# PowerLatch.net
KiCad netlist of a schematic drawn in Altium Designer
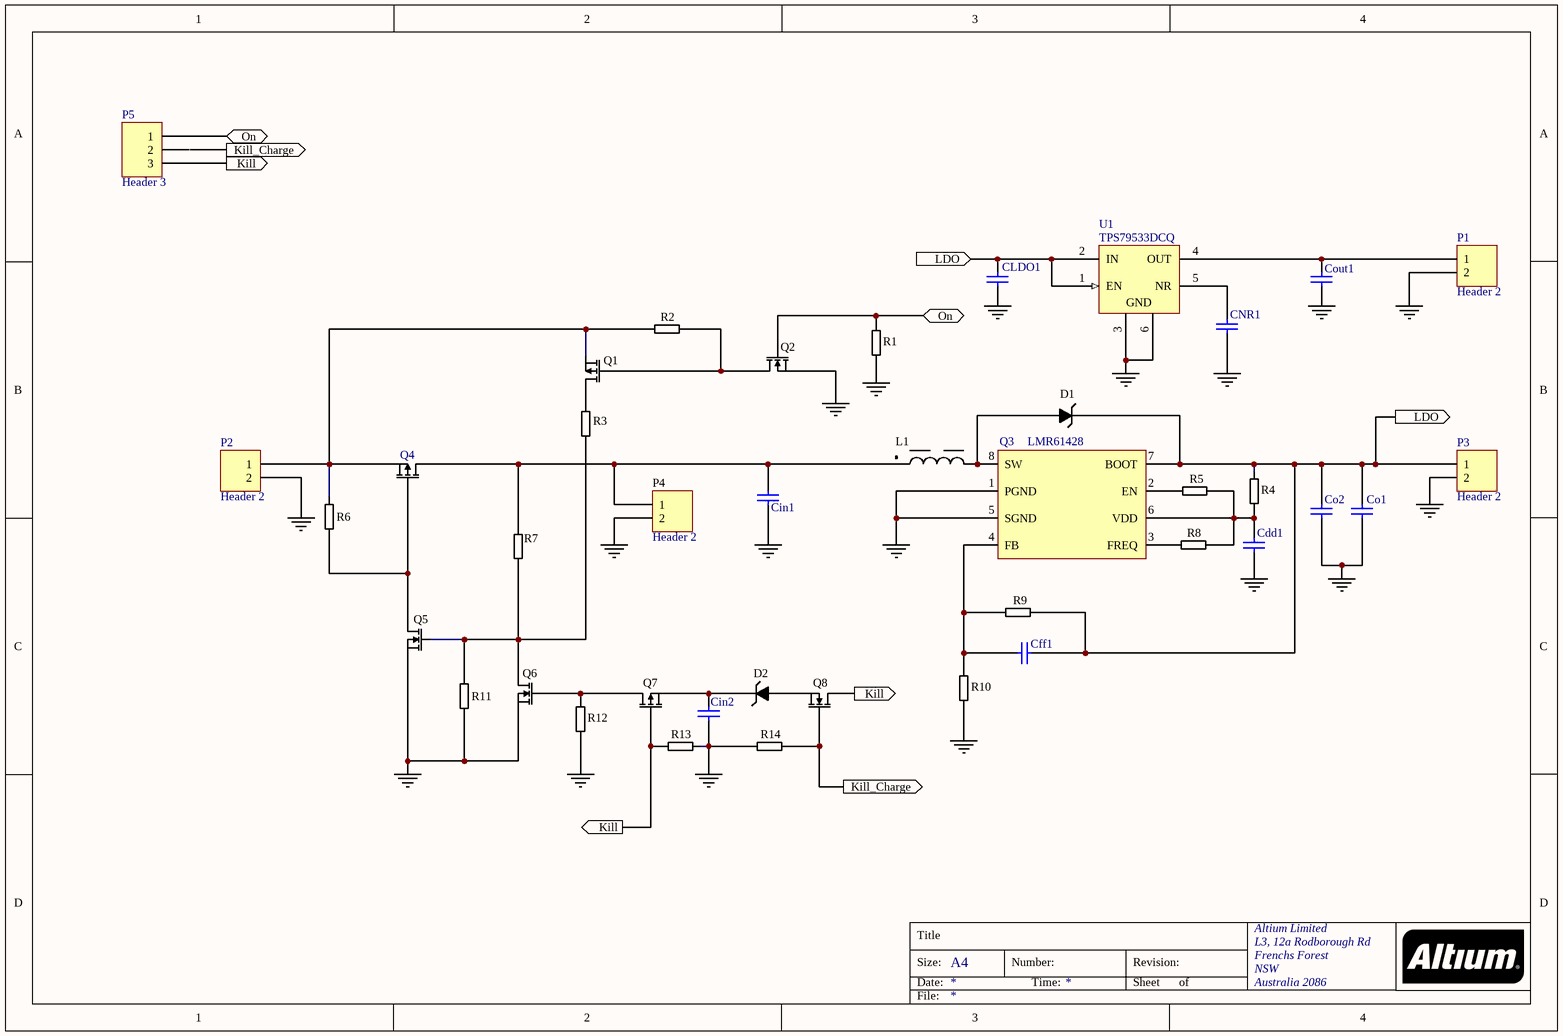
[diagram p0: PowerLatch.SchDoc]

(export (version "E")
  (design (tool "Eeschema 10.0.6"))
  (components
    (comp (ref "Cdd1")
      (value "Cap")
      (footprint "RESC1608X06N")
      (description "Capacitor")
      (fields (field (name "PUBLISHER") "Altium Limited"))
      (libsource (lib "Miscellaneous Devices") (part "Cap"))
    )
    (comp (ref "Cff1")
      (value "Cap")
      (footprint "RESC1608X06N")
      (description "Capacitor")
      (fields (field (name "PUBLISHER") "Altium Limited"))
      (libsource (lib "Miscellaneous Devices") (part "Cap"))
    )
    (comp (ref "Cin1")
      (value "Cap")
      (footprint "CAPMP7343X31N")
      (description "Capacitor")
      (fields (field (name "PUBLISHER") "Altium Limited"))
      (libsource (lib "Miscellaneous Devices") (part "Cap"))
    )
    (comp (ref "Cin2")
      (value "Cap")
      (footprint "CAPMP7343X31N")
      (description "Capacitor")
      (fields (field (name "PUBLISHER") "Altium Limited"))
      (libsource (lib "Miscellaneous Devices") (part "Cap"))
    )
    (comp (ref "CLDO1")
      (value "Cap")
      (footprint "RESC1608X06N")
      (description "Capacitor")
      (fields (field (name "PUBLISHER") "Altium Limited"))
      (libsource (lib "Miscellaneous Devices") (part "Cap"))
    )
    (comp (ref "CNR1")
      (value "Cap")
      (footprint "RESC1608X06N")
      (description "Capacitor")
      (fields (field (name "PUBLISHER") "Altium Limited"))
      (libsource (lib "Miscellaneous Devices") (part "Cap"))
    )
    (comp (ref "Co1")
      (value "Cap")
      (footprint "CAPC0805")
      (description "Capacitor")
      (fields (field (name "PUBLISHER") "Altium Limited"))
      (libsource (lib "Miscellaneous Devices") (part "Cap"))
    )
    (comp (ref "Co2")
      (value "Cap")
      (footprint "CAP2812")
      (description "Capacitor")
      (fields (field (name "PUBLISHER") "Altium Limited"))
      (libsource (lib "Miscellaneous Devices") (part "Cap"))
    )
    (comp (ref "Cout1")
      (value "Cap")
      (footprint "RESC1608X06N")
      (description "Capacitor")
      (fields (field (name "PUBLISHER") "Altium Limited"))
      (libsource (lib "Miscellaneous Devices") (part "Cap"))
    )
    (comp (ref "D1")
      (value "Schottky")
      (footprint "DIOM4326X23N")
      (libsource (lib "Schlib1") (part "Schottky"))
    )
    (comp (ref "D2")
      (value "Schottky")
      (footprint "DIOM4326X23N")
      (libsource (lib "Schlib1") (part "Schottky"))
    )
    (comp (ref "L1")
      (value "Inductor")
      (footprint "INDP100100X51N")
      (libsource (lib "Schlib1") (part "Inductor"))
    )
    (comp (ref "P1")
      (value "Header 2")
      (footprint "PCBComponent_1")
      (description "Header, 2-Pin")
      (fields (field (name "PUBLISHER") "Altium Limited"))
      (libsource (lib "") (part "Header 2_1"))
    )
    (comp (ref "P2")
      (value "Header 2")
      (footprint "PCBComponent_1")
      (description "Header, 2-Pin")
      (fields (field (name "PUBLISHER") "Altium Limited"))
      (libsource (lib "Miscellaneous Connectors") (part "Header 2"))
    )
    (comp (ref "P3")
      (value "Header 2")
      (footprint "PCBComponent_1")
      (description "Header, 2-Pin")
      (fields (field (name "PUBLISHER") "Altium Limited"))
      (libsource (lib "") (part "Header 2_1"))
    )
    (comp (ref "P4")
      (value "Header 2")
      (footprint "PCBComponent_1")
      (description "Header, 2-Pin")
      (fields (field (name "PUBLISHER") "Altium Limited"))
      (libsource (lib "") (part "Header 2_1"))
    )
    (comp (ref "P5")
      (value "Header 3")
      (footprint "HDR1X3")
      (description "Header, 3-Pin")
      (fields (field (name "PUBLISHER") "Altium Limited"))
      (libsource (lib "Miscellaneous Connectors") (part "Header 3"))
    )
    (comp (ref "Q1")
      (value "MOSFET P-Channel")
      (footprint "SOT95P245X110-3N")
      (libsource (lib "Schlib1") (part "MOSFET P-Channel"))
    )
    (comp (ref "Q2")
      (value "MOSFET N-Channel")
      (footprint "SOT95P245X110-3N")
      (libsource (lib "Schlib1") (part "MOSFET N-Channel"))
    )
    (comp (ref "Q3")
      (value "LMR61428")
      (footprint "TSOP65P490X110-8N")
      (description "Step-Up Voltage Regulator")
      (libsource (lib "Schlib1") (part "LMR61428"))
    )
    (comp (ref "Q4")
      (value "MOSFET P-Channel")
      (footprint "SOT95P245X110-3N")
      (libsource (lib "Schlib1") (part "MOSFET P-Channel"))
    )
    (comp (ref "Q5")
      (value "MOSFET N-Channel")
      (footprint "SOT95P245X110-3N")
      (libsource (lib "Schlib1") (part "MOSFET N-Channel"))
    )
    (comp (ref "Q6")
      (value "MOSFET N-Channel")
      (footprint "SOT95P245X110-3N")
      (libsource (lib "Schlib1") (part "MOSFET N-Channel"))
    )
    (comp (ref "Q7")
      (value "MOSFET P-Channel")
      (footprint "SOT95P245X110-3N")
      (libsource (lib "Schlib1") (part "MOSFET P-Channel"))
    )
    (comp (ref "Q8")
      (value "MOSFET N-Channel")
      (footprint "SOT95P245X110-3N")
      (libsource (lib "Schlib1") (part "MOSFET N-Channel"))
    )
    (comp (ref "R1") (value "Res?") (libsource (lib "Schlib1") (part "Res?")))
    (comp (ref "R2") (value "Res?") (libsource (lib "Schlib1") (part "Res?")))
    (comp (ref "R3") (value "Res?") (libsource (lib "Schlib1") (part "Res?")))
    (comp (ref "R4") (value "Res?") (libsource (lib "Schlib1") (part "Res?")))
    (comp (ref "R5") (value "Res?") (libsource (lib "Schlib1") (part "Res?")))
    (comp (ref "R6") (value "Res?") (libsource (lib "Schlib1") (part "Res?")))
    (comp (ref "R7") (value "Res?") (libsource (lib "Schlib1") (part "Res?")))
    (comp (ref "R8") (value "Res?") (libsource (lib "Schlib1") (part "Res?")))
    (comp (ref "R9") (value "Res?") (libsource (lib "Schlib1") (part "Res?")))
    (comp (ref "R10") (value "Res?") (libsource (lib "Schlib1") (part "Res?")))
    (comp (ref "R11") (value "Res?") (libsource (lib "Schlib1") (part "Res?")))
    (comp (ref "R12") (value "Res?") (libsource (lib "Schlib1") (part "Res?")))
    (comp (ref "R13") (value "Res?") (libsource (lib "Schlib1") (part "Res?")))
    (comp (ref "R14") (value "Res?") (libsource (lib "Schlib1") (part "Res?")))
    (comp (ref "U1")
      (value "TPS79533DCQ")
      (footprint "DCQ0006A_L")
      (fields (field (name "MANUFACTURER") "Texas Instruments"))
      (libsource (lib "Altium Content Vault") (part "TI-TPS7XXXXXXXX"))
    )
  )
  (nets
    (net (code "1") (name "/Kill") (class "Default")
      (node (ref "P5") (pin "3") (pinfunction "3_3") (pintype "passive"))
      (node (ref "Q7") (pin "1") (pinfunction "G_1") (pintype "passive"))
      (node (ref "Q8") (pin "3") (pinfunction "D_3") (pintype "passive"))
      (node (ref "R13") (pin "2") (pinfunction "2_2") (pintype "passive"))
    )
    (net (code "2") (name "/Kill_Charge") (class "Default")
      (node (ref "Q8") (pin "1") (pinfunction "G_1") (pintype "passive"))
      (node (ref "R14") (pin "1") (pinfunction "1_1") (pintype "passive"))
    )
    (net (code "3") (name "/LDO") (class "Default")
      (node (ref "CLDO1") (pin "2") (pinfunction "2_2") (pintype "passive"))
      (node (ref "Cff1") (pin "1") (pinfunction "1_1") (pintype "passive"))
      (node (ref "Co1") (pin "2") (pinfunction "2_2") (pintype "passive"))
      (node (ref "Co2") (pin "1") (pinfunction "1_1") (pintype "passive"))
      (node (ref "D1") (pin "2") (pinfunction "K_2") (pintype "passive"))
      (node (ref "P3") (pin "1") (pinfunction "1_1") (pintype "passive"))
      (node (ref "Q3") (pin "7") (pinfunction "BOOT_7") (pintype "passive"))
      (node (ref "R4") (pin "2") (pinfunction "2_2") (pintype "passive"))
      (node (ref "R9") (pin "1") (pinfunction "1_1") (pintype "passive"))
      (node (ref "U1") (pin "1") (pinfunction "EN_1") (pintype "input"))
      (node (ref "U1") (pin "2") (pinfunction "IN_2") (pintype "power_in"))
    )
    (net (code "4") (name "/On") (class "Default")
      (node (ref "P5") (pin "1") (pinfunction "1_1") (pintype "passive"))
      (node (ref "Q2") (pin "1") (pinfunction "G_1") (pintype "passive"))
      (node (ref "R1") (pin "2") (pinfunction "2_2") (pintype "passive"))
    )
    (net (code "5") (name "GND") (class "Default")
      (node (ref "CLDO1") (pin "1") (pinfunction "1_1") (pintype "passive"))
      (node (ref "CNR1") (pin "1") (pinfunction "1_1") (pintype "passive"))
      (node (ref "Cdd1") (pin "1") (pinfunction "1_1") (pintype "passive"))
      (node (ref "Cin1") (pin "2") (pinfunction "2_2") (pintype "passive"))
      (node (ref "Cin2") (pin "2") (pinfunction "2_2") (pintype "passive"))
      (node (ref "Co1") (pin "1") (pinfunction "1_1") (pintype "passive"))
      (node (ref "Co2") (pin "2") (pinfunction "2_2") (pintype "passive"))
      (node (ref "Cout1") (pin "1") (pinfunction "1_1") (pintype "passive"))
      (node (ref "P1") (pin "2") (pinfunction "2_2") (pintype "passive"))
      (node (ref "P2") (pin "2") (pinfunction "2_2") (pintype "passive"))
      (node (ref "P3") (pin "2") (pinfunction "2_2") (pintype "passive"))
      (node (ref "P4") (pin "2") (pinfunction "2_2") (pintype "passive"))
      (node (ref "Q2") (pin "2") (pinfunction "S_2") (pintype "passive"))
      (node (ref "Q3") (pin "1") (pinfunction "PGND_1") (pintype "passive"))
      (node (ref "Q3") (pin "5") (pinfunction "SGND_5") (pintype "passive"))
      (node (ref "Q5") (pin "2") (pinfunction "S_2") (pintype "passive"))
      (node (ref "Q6") (pin "2") (pinfunction "S_2") (pintype "passive"))
      (node (ref "R1") (pin "1") (pinfunction "1_1") (pintype "passive"))
      (node (ref "R10") (pin "1") (pinfunction "1_1") (pintype "passive"))
      (node (ref "R11") (pin "1") (pinfunction "1_1") (pintype "passive"))
      (node (ref "R12") (pin "1") (pinfunction "1_1") (pintype "passive"))
      (node (ref "R13") (pin "1") (pinfunction "1_1") (pintype "passive"))
      (node (ref "R14") (pin "2") (pinfunction "2_2") (pintype "passive"))
      (node (ref "U1") (pin "3") (pinfunction "GND_3") (pintype "power_in"))
      (node (ref "U1") (pin "6") (pinfunction "GND_6") (pintype "power_in"))
    )
    (net (code "6") (name "Net-(D1-A)") (class "Default")
      (node (ref "D1") (pin "1") (pinfunction "A_1") (pintype "passive"))
      (node (ref "L1") (pin "2") (pinfunction "2_2") (pintype "passive"))
      (node (ref "Q3") (pin "8") (pinfunction "SW_8") (pintype "passive"))
    )
    (net (code "7") (name "Net-(D2-A)") (class "Default")
      (node (ref "D2") (pin "1") (pinfunction "A_1") (pintype "passive"))
      (node (ref "Q8") (pin "2") (pinfunction "S_2") (pintype "passive"))
    )
    (net (code "8") (name "Net-(D2-K)") (class "Default")
      (node (ref "Cin2") (pin "1") (pinfunction "1_1") (pintype "passive"))
      (node (ref "D2") (pin "2") (pinfunction "K_2") (pintype "passive"))
      (node (ref "Q7") (pin "2") (pinfunction "S_2") (pintype "passive"))
    )
    (net (code "9") (name "Net-(Q1-D)") (class "Default")
      (node (ref "Q1") (pin "3") (pinfunction "D_3") (pintype "passive"))
      (node (ref "R3") (pin "2") (pinfunction "2_2") (pintype "passive"))
    )
    (net (code "10") (name "Net-(Q1-G)") (class "Default")
      (node (ref "Q1") (pin "1") (pinfunction "G_1") (pintype "passive"))
      (node (ref "Q2") (pin "3") (pinfunction "D_3") (pintype "passive"))
      (node (ref "R2") (pin "1") (pinfunction "1_1") (pintype "passive"))
    )
    (net (code "11") (name "Net-(Q1-S)") (class "Default")
      (node (ref "P2") (pin "1") (pinfunction "1_1") (pintype "passive"))
      (node (ref "Q1") (pin "2") (pinfunction "S_2") (pintype "passive"))
      (node (ref "Q4") (pin "2") (pinfunction "S_2") (pintype "passive"))
      (node (ref "R2") (pin "2") (pinfunction "2_2") (pintype "passive"))
      (node (ref "R6") (pin "2") (pinfunction "2_2") (pintype "passive"))
    )
    (net (code "12") (name "Net-(Q3-EN)") (class "Default")
      (node (ref "Q3") (pin "2") (pinfunction "EN_2") (pintype "passive"))
      (node (ref "R5") (pin "2") (pinfunction "2_2") (pintype "passive"))
    )
    (net (code "13") (name "Net-(Q3-FB)") (class "Default")
      (node (ref "Cff1") (pin "2") (pinfunction "2_2") (pintype "passive"))
      (node (ref "Q3") (pin "4") (pinfunction "FB_4") (pintype "passive"))
      (node (ref "R10") (pin "2") (pinfunction "2_2") (pintype "passive"))
      (node (ref "R9") (pin "2") (pinfunction "2_2") (pintype "passive"))
    )
    (net (code "14") (name "Net-(Q3-FREQ)") (class "Default")
      (node (ref "Q3") (pin "3") (pinfunction "FREQ_3") (pintype "passive"))
      (node (ref "R8") (pin "2") (pinfunction "2_2") (pintype "passive"))
    )
    (net (code "15") (name "Net-(Q3-VDD)") (class "Default")
      (node (ref "Cdd1") (pin "2") (pinfunction "2_2") (pintype "passive"))
      (node (ref "Q3") (pin "6") (pinfunction "VDD_6") (pintype "passive"))
      (node (ref "R4") (pin "1") (pinfunction "1_1") (pintype "passive"))
      (node (ref "R5") (pin "1") (pinfunction "1_1") (pintype "passive"))
      (node (ref "R8") (pin "1") (pinfunction "1_1") (pintype "passive"))
    )
    (net (code "16") (name "Net-(Q4-D)") (class "Default")
      (node (ref "Cin1") (pin "1") (pinfunction "1_1") (pintype "passive"))
      (node (ref "L1") (pin "1") (pinfunction "1_1") (pintype "passive"))
      (node (ref "P4") (pin "1") (pinfunction "1_1") (pintype "passive"))
      (node (ref "Q4") (pin "3") (pinfunction "D_3") (pintype "passive"))
      (node (ref "R7") (pin "2") (pinfunction "2_2") (pintype "passive"))
    )
    (net (code "17") (name "Net-(Q4-G)") (class "Default")
      (node (ref "Q4") (pin "1") (pinfunction "G_1") (pintype "passive"))
      (node (ref "Q5") (pin "3") (pinfunction "D_3") (pintype "passive"))
      (node (ref "R6") (pin "1") (pinfunction "1_1") (pintype "passive"))
    )
    (net (code "18") (name "Net-(Q5-G)") (class "Default")
      (node (ref "Q5") (pin "1") (pinfunction "G_1") (pintype "passive"))
      (node (ref "Q6") (pin "3") (pinfunction "D_3") (pintype "passive"))
      (node (ref "R11") (pin "2") (pinfunction "2_2") (pintype "passive"))
      (node (ref "R3") (pin "1") (pinfunction "1_1") (pintype "passive"))
      (node (ref "R7") (pin "1") (pinfunction "1_1") (pintype "passive"))
    )
    (net (code "19") (name "Net-(Q6-G)") (class "Default")
      (node (ref "Q6") (pin "1") (pinfunction "G_1") (pintype "passive"))
      (node (ref "Q7") (pin "3") (pinfunction "D_3") (pintype "passive"))
      (node (ref "R12") (pin "2") (pinfunction "2_2") (pintype "passive"))
    )
    (net (code "20") (name "Net-(U1-NR)") (class "Default")
      (node (ref "CNR1") (pin "2") (pinfunction "2_2") (pintype "passive"))
      (node (ref "U1") (pin "5") (pinfunction "NR_5") (pintype "passive"))
    )
    (net (code "21") (name "Net-(U1-OUT)") (class "Default")
      (node (ref "Cout1") (pin "2") (pinfunction "2_2") (pintype "passive"))
      (node (ref "P1") (pin "1") (pinfunction "1_1") (pintype "passive"))
      (node (ref "U1") (pin "4") (pinfunction "OUT_4") (pintype "power_in"))
    )
    (net (code "22") (name "unconnected-(P5-Pad2)") (class "Default")
      (node (ref "P5") (pin "2") (pinfunction "2_2") (pintype "passive"))
    )
  )
)
